# fonte.net
KiCad netlist of a schematic drawn in EAGLE
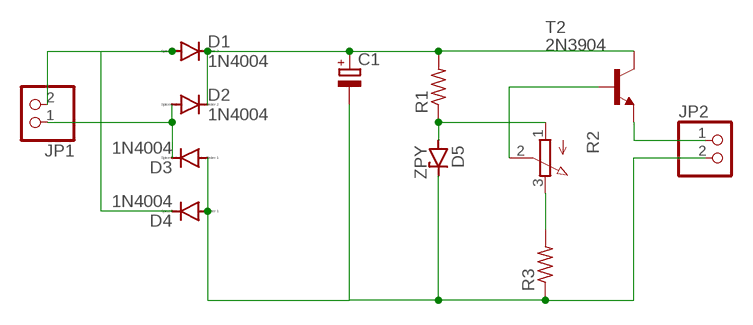
[diagram p0: schematic, sheet 1]

(export (version "E")
  (design (tool "Eeschema 10.0.6"))
  (components
    (comp (ref "C1")
      (value "CPOL-EUE3.5-10")
      (footprint "eagle-import:E3,5-10")
      (libsource (lib "eagle-import") (part "CPOL-EUE3.5-10"))
    )
    (comp (ref "D1")
      (value "1N4004")
      (footprint "eagle-import:DO41-10")
      (libsource (lib "eagle-import") (part "1N4004"))
    )
    (comp (ref "D2")
      (value "1N4004")
      (footprint "eagle-import:DO41-10")
      (libsource (lib "eagle-import") (part "1N4004"))
    )
    (comp (ref "D3")
      (value "1N4004")
      (footprint "eagle-import:DO41-10")
      (libsource (lib "eagle-import") (part "1N4004"))
    )
    (comp (ref "D4")
      (value "1N4004")
      (footprint "eagle-import:DO41-10")
      (libsource (lib "eagle-import") (part "1N4004"))
    )
    (comp (ref "D5")
      (value "ZPY")
      (footprint "eagle-import:DO41Z10")
      (libsource (lib "eagle-import") (part "ZPY"))
    )
    (comp (ref "JP1")
      (value "PINHD-1X2")
      (footprint "eagle-import:1X02")
      (libsource (lib "eagle-import") (part "PINHD-1X2"))
    )
    (comp (ref "JP2")
      (value "PINHD-1X2")
      (footprint "eagle-import:1X02")
      (libsource (lib "eagle-import") (part "PINHD-1X2"))
    )
    (comp (ref "R1")
      (value "R-US_0207/10")
      (footprint "eagle-import:0207_10")
      (libsource (lib "eagle-import") (part "R-US_0207/10"))
    )
    (comp (ref "R2")
      (value "3RP/1610N")
      (footprint "eagle-import:3RP_1610N")
      (libsource (lib "eagle-import") (part "3RP/1610N"))
    )
    (comp (ref "R3")
      (value "R-US_0207/10")
      (footprint "eagle-import:0207_10")
      (libsource (lib "eagle-import") (part "R-US_0207/10"))
    )
    (comp (ref "T2")
      (value "2N3904")
      (footprint "eagle-import:TO92")
      (libsource (lib "eagle-import") (part "2N3904"))
    )
  )
  (nets
    (net (code "1") (name "Net-(C1-Pad-)") (class "Default")
      (node (ref "C1") (pin "-") (pinfunction "-_-") (pintype "passive"))
      (node (ref "D3") (pin "A") (pinfunction "A_A") (pintype "passive"))
      (node (ref "D4") (pin "A") (pinfunction "A_A") (pintype "passive"))
      (node (ref "D5") (pin "C") (pinfunction "C_C") (pintype "passive"))
      (node (ref "JP2") (pin "2") (pinfunction "2_2") (pintype "passive"))
      (node (ref "R3") (pin "1") (pinfunction "1_1") (pintype "passive"))
    )
    (net (code "2") (name "Net-(D1-PadA)") (class "Default")
      (node (ref "D1") (pin "A") (pinfunction "A_A") (pintype "passive"))
      (node (ref "D4") (pin "C") (pinfunction "C_C") (pintype "passive"))
      (node (ref "JP1") (pin "2") (pinfunction "2_2") (pintype "passive"))
    )
    (net (code "3") (name "Net-(D2-PadA)") (class "Default")
      (node (ref "D2") (pin "A") (pinfunction "A_A") (pintype "passive"))
      (node (ref "D3") (pin "C") (pinfunction "C_C") (pintype "passive"))
      (node (ref "JP1") (pin "1") (pinfunction "1_1") (pintype "passive"))
    )
    (net (code "4") (name "Net-(R2-A)") (class "Default")
      (node (ref "D5") (pin "A") (pinfunction "A_A") (pintype "passive"))
      (node (ref "R1") (pin "1") (pinfunction "1_1") (pintype "passive"))
      (node (ref "R2") (pin "1") (pinfunction "A_1") (pintype "passive"))
    )
    (net (code "5") (name "Net-(R2-E)") (class "Default")
      (node (ref "R2") (pin "3") (pinfunction "E_3") (pintype "passive"))
      (node (ref "R3") (pin "2") (pinfunction "2_2") (pintype "passive"))
    )
    (net (code "6") (name "Net-(R2-S)") (class "Default")
      (node (ref "R2") (pin "2") (pinfunction "S_2") (pintype "passive"))
      (node (ref "T2") (pin "2") (pinfunction "B_2") (pintype "passive"))
    )
    (net (code "7") (name "Net-(T2-C)") (class "Default")
      (node (ref "C1") (pin "+") (pinfunction "+_+") (pintype "passive"))
      (node (ref "D1") (pin "C") (pinfunction "C_C") (pintype "passive"))
      (node (ref "D2") (pin "C") (pinfunction "C_C") (pintype "passive"))
      (node (ref "R1") (pin "2") (pinfunction "2_2") (pintype "passive"))
      (node (ref "T2") (pin "1") (pinfunction "C_1") (pintype "passive"))
    )
    (net (code "8") (name "Net-(T2-E)") (class "Default")
      (node (ref "JP2") (pin "1") (pinfunction "1_1") (pintype "passive"))
      (node (ref "T2") (pin "3") (pinfunction "E_3") (pintype "passive"))
    )
  )
)
